# DispenserV2_0.net
KiCad netlist of a schematic drawn in EAGLE
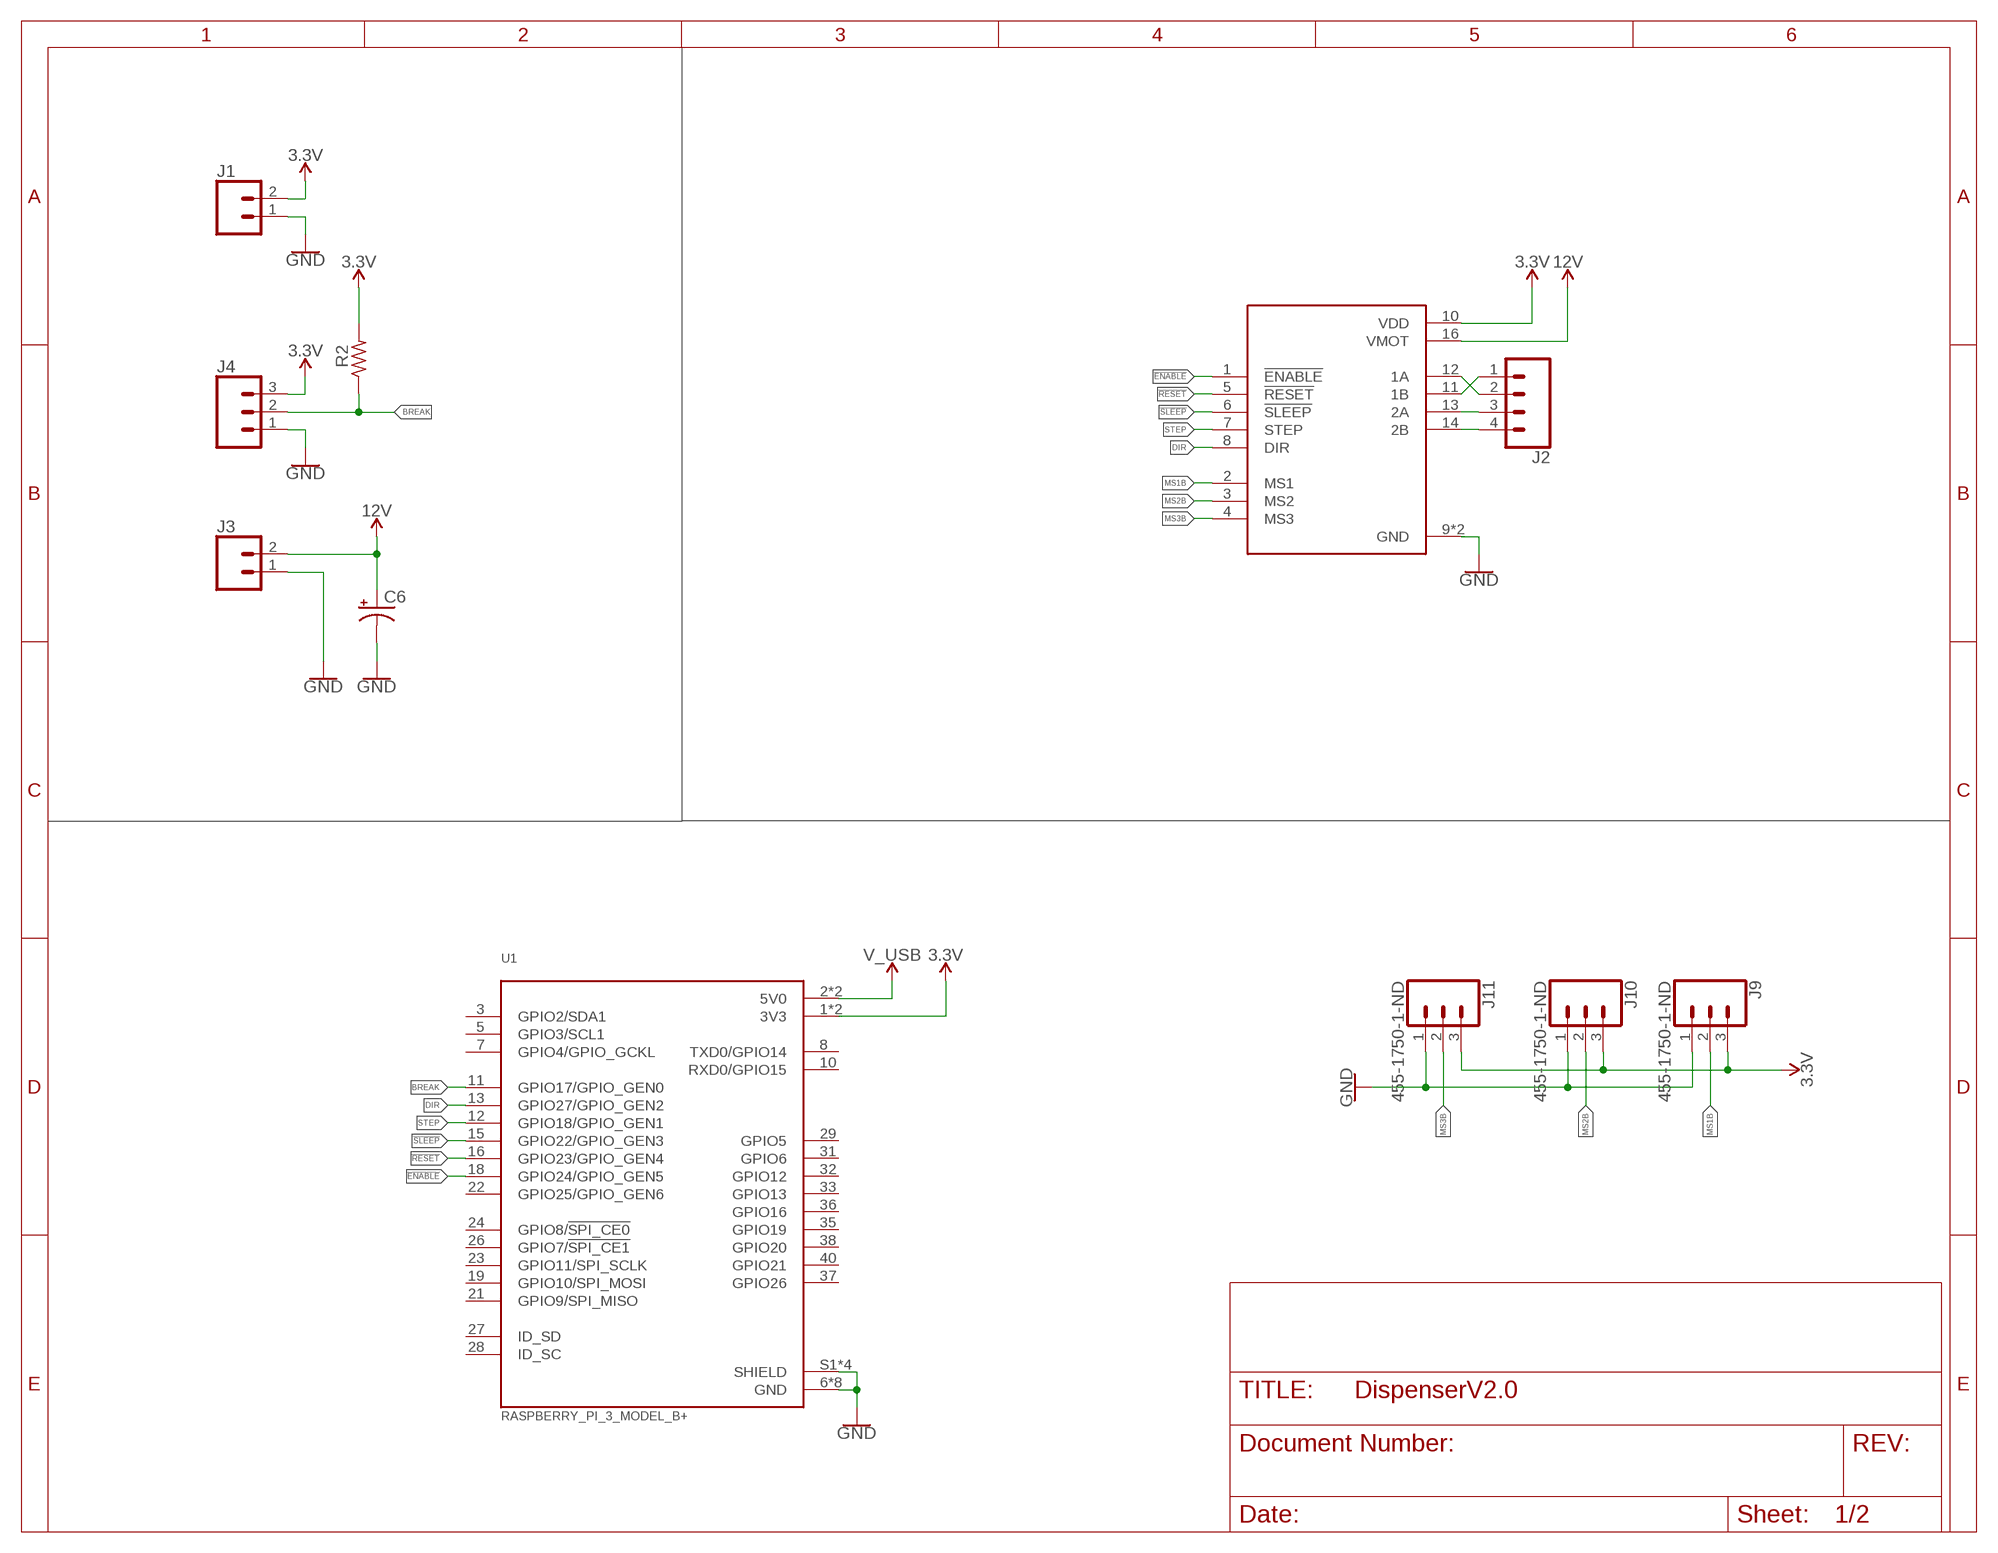
[diagram p0: schematic, sheet 1]
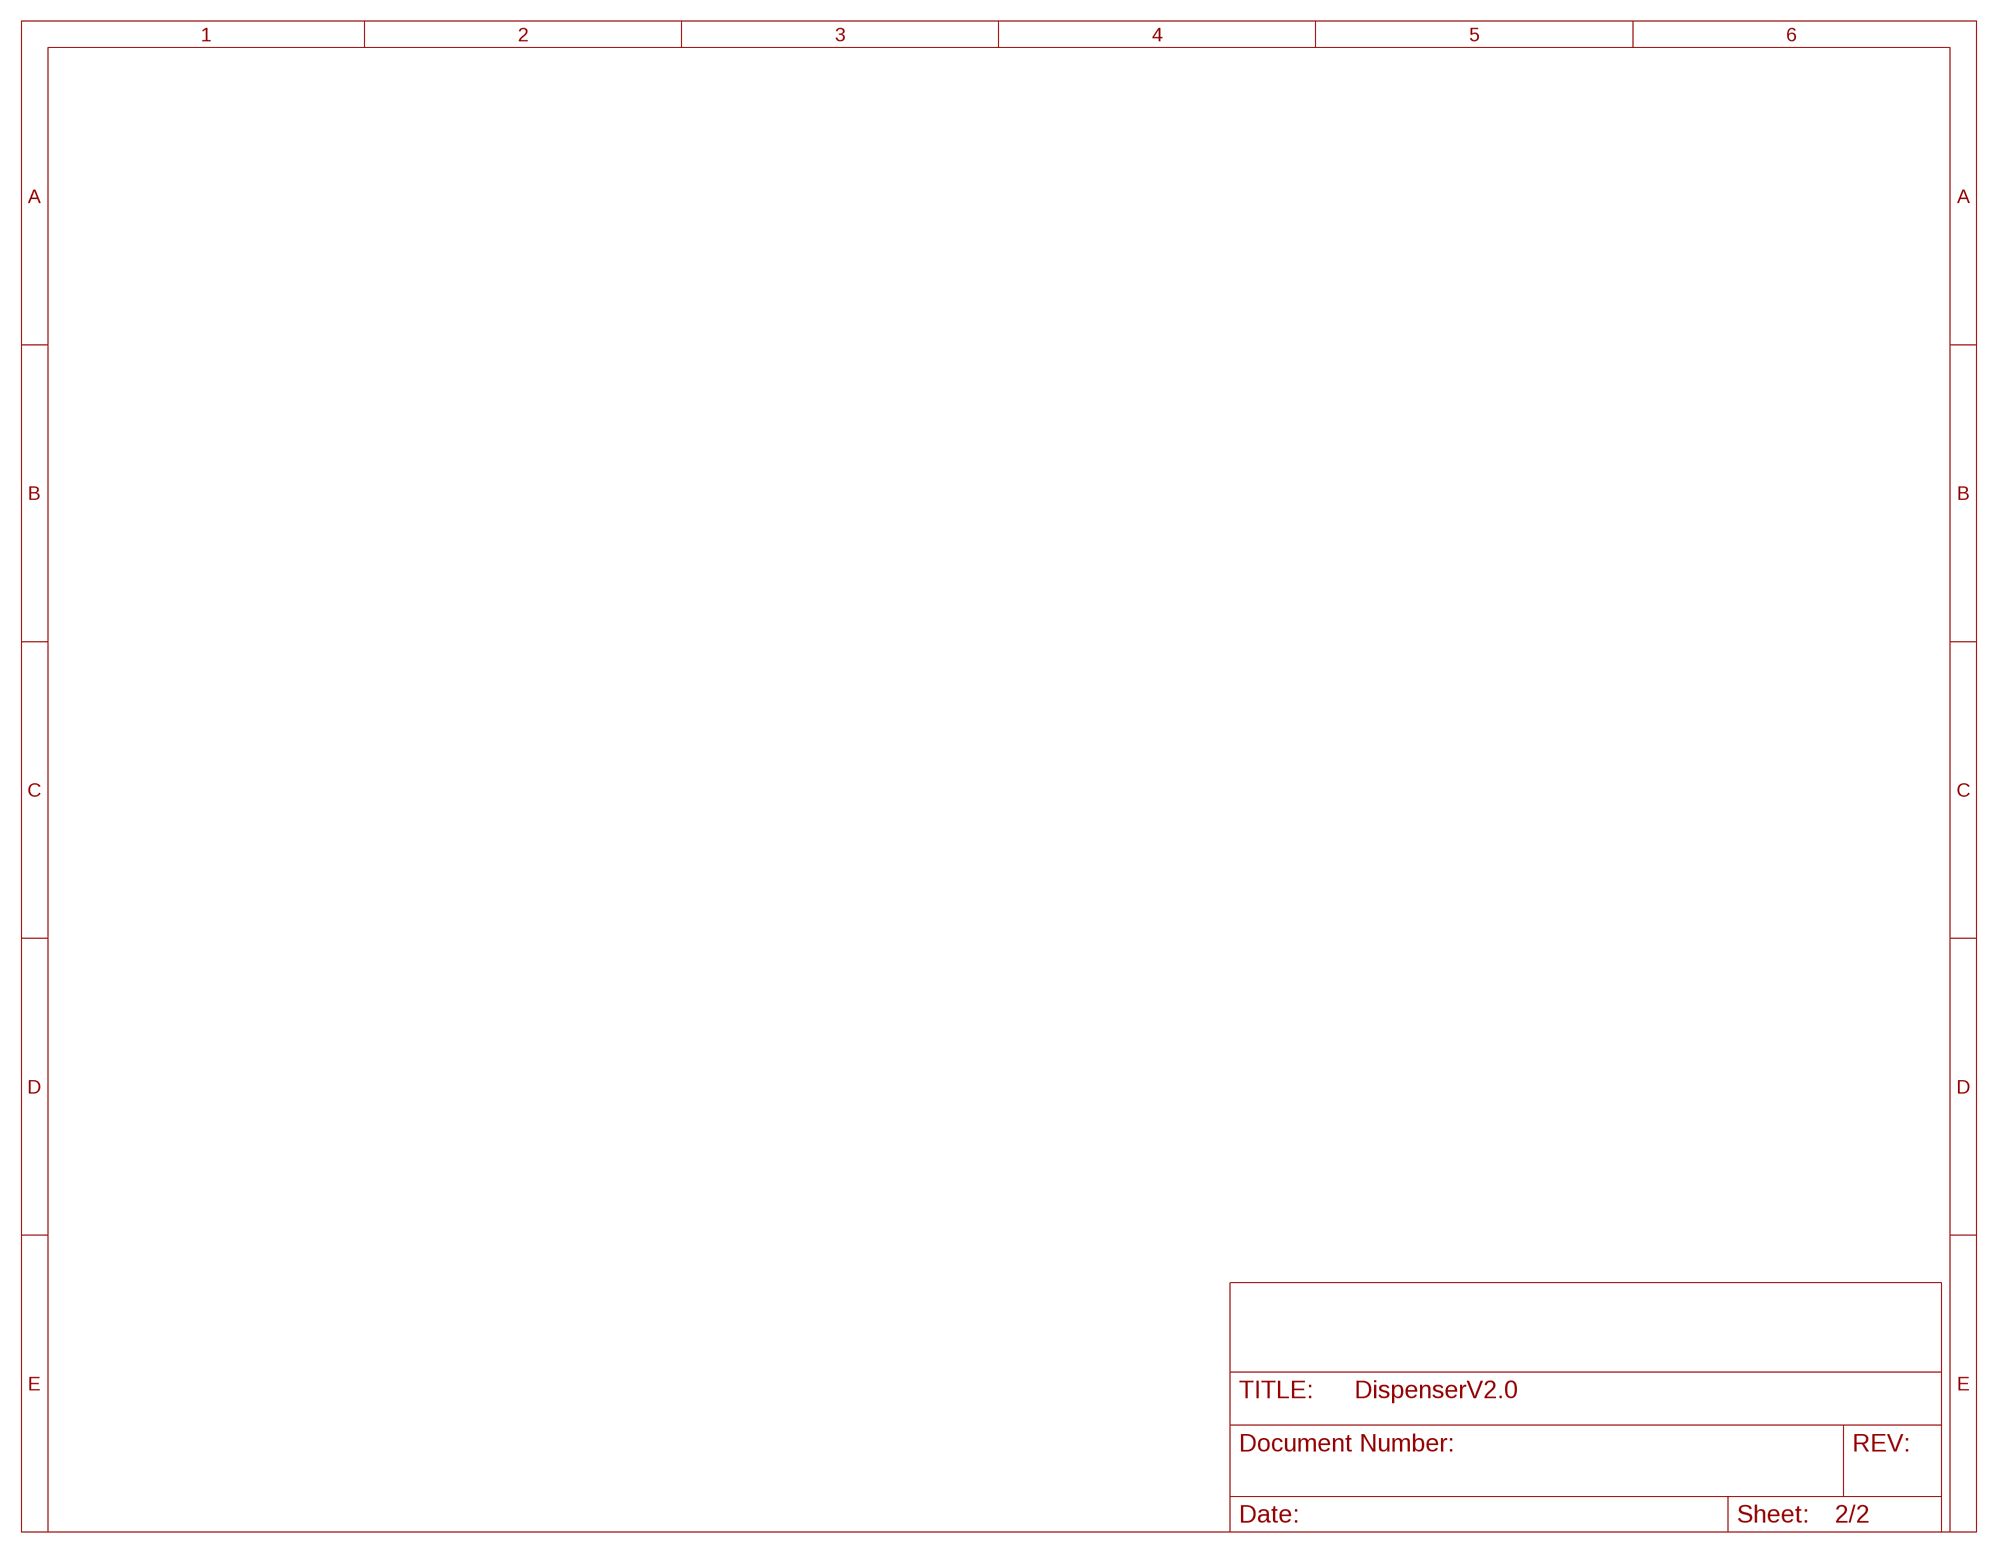
[diagram p1: schematic, sheet 2]

(export (version "E")
  (design (tool "Eeschema 10.0.6"))
  (components
    (comp (ref "C6")
      (value "CPOL-USE2-5")
      (footprint "eagle-import:E2-5")
      (libsource (lib "eagle-import") (part "CPOL-USE2-5"))
    )
    (comp (ref "J1")
      (value "CONN_023.5MM")
      (footprint "eagle-import:SCREWTERMINAL-3.5MM-2")
      (libsource (lib "eagle-import") (part "CONN_023.5MM"))
    )
    (comp (ref "J2")
      (value "CONN_04")
      (footprint "eagle-import:1X04")
      (libsource (lib "eagle-import") (part "CONN_04"))
    )
    (comp (ref "J3")
      (value "CONN_023.5MM")
      (footprint "eagle-import:SCREWTERMINAL-3.5MM-2")
      (libsource (lib "eagle-import") (part "CONN_023.5MM"))
    )
    (comp (ref "J4")
      (value "CONN_03SCREW")
      (footprint "eagle-import:SCREWTERMINAL-3.5MM-3")
      (libsource (lib "eagle-import") (part "CONN_03SCREW"))
    )
    (comp (ref "J9")
      (value "455-1750-1-ND")
      (footprint "eagle-import:1X03")
      (libsource (lib "eagle-import") (part "CONN_03"))
    )
    (comp (ref "J10")
      (value "455-1750-1-ND")
      (footprint "eagle-import:1X03")
      (libsource (lib "eagle-import") (part "CONN_03"))
    )
    (comp (ref "J11")
      (value "455-1750-1-ND")
      (footprint "eagle-import:1X03")
      (libsource (lib "eagle-import") (part "CONN_03"))
    )
    (comp (ref "R2")
      (value "R-US_0207/10")
      (footprint "eagle-import:0207_10")
      (libsource (lib "eagle-import") (part "R-US_0207/10"))
    )
    (comp (ref "U1")
      (value "RASPBERRY_PI_3_MODEL_B+")
      (footprint "eagle-import:MODULE_RASPBERRY_PI_3_MODEL_B+")
      (fields (field (name "MF") "Raspberry Pi") (field (name "MP") "RASPBERRY PI 3 MODEL B+"))
      (libsource (lib "eagle-import") (part "RASPBERRY_PI_3_MODEL_B+"))
    )
    (comp (ref "U2")
      (value "A4988")
      (footprint "eagle-import:MODULE_A4988_STEPPER_MOTOR_DRIVER_CARRIER")
      (fields (field (name "MF") "Pololu") (field (name "MP") "A4988 STEPPER MOTOR DRIVER CARRIER"))
      (libsource (lib "eagle-import") (part "A4988_STEPPER_MOTOR_DRIVER_CARRIER"))
    )
  )
  (nets
    (net (code "1") (name "3.3V") (class "Default")
      (node (ref "J1") (pin "2") (pinfunction "2_2") (pintype "passive"))
      (node (ref "J10") (pin "3") (pinfunction "3_3") (pintype "passive"))
      (node (ref "J11") (pin "3") (pinfunction "3_3") (pintype "passive"))
      (node (ref "J4") (pin "3") (pinfunction "3_3") (pintype "passive"))
      (node (ref "J9") (pin "3") (pinfunction "3_3") (pintype "passive"))
      (node (ref "R2") (pin "2") (pinfunction "2_2") (pintype "passive"))
      (node (ref "U1") (pin "1") (pinfunction "3V3_1") (pintype "power_in"))
      (node (ref "U1") (pin "17") (pinfunction "3V3_17") (pintype "power_in"))
      (node (ref "U2") (pin "10") (pinfunction "VDD_10") (pintype "power_in"))
    )
    (net (code "2") (name "12V") (class "Default")
      (node (ref "C6") (pin "+") (pinfunction "+_+") (pintype "passive"))
      (node (ref "J3") (pin "2") (pinfunction "2_2") (pintype "passive"))
      (node (ref "U2") (pin "16") (pinfunction "VMOT_16") (pintype "power_in"))
    )
    (net (code "3") (name "BREAK") (class "Default")
      (node (ref "J4") (pin "2") (pinfunction "2_2") (pintype "passive"))
      (node (ref "R2") (pin "1") (pinfunction "1_1") (pintype "passive"))
      (node (ref "U1") (pin "11") (pinfunction "GPIO17/GPIO_GEN0_11") (pintype "bidirectional"))
    )
    (net (code "4") (name "DIR") (class "Default")
      (node (ref "U1") (pin "13") (pinfunction "GPIO27/GPIO_GEN2_13") (pintype "bidirectional"))
      (node (ref "U2") (pin "8") (pinfunction "DIR_8") (pintype "input"))
    )
    (net (code "5") (name "GND") (class "Default")
      (node (ref "C6") (pin "-") (pinfunction "-_-") (pintype "passive"))
      (node (ref "J1") (pin "1") (pinfunction "1_1") (pintype "passive"))
      (node (ref "J10") (pin "1") (pinfunction "1_1") (pintype "passive"))
      (node (ref "J11") (pin "1") (pinfunction "1_1") (pintype "passive"))
      (node (ref "J3") (pin "1") (pinfunction "1_1") (pintype "passive"))
      (node (ref "J4") (pin "1") (pinfunction "1_1") (pintype "passive"))
      (node (ref "J9") (pin "1") (pinfunction "1_1") (pintype "passive"))
      (node (ref "U1") (pin "14") (pinfunction "GND_14") (pintype "power_in"))
      (node (ref "U1") (pin "20") (pinfunction "GND_20") (pintype "power_in"))
      (node (ref "U1") (pin "25") (pinfunction "GND_25") (pintype "power_in"))
      (node (ref "U1") (pin "30") (pinfunction "GND_30") (pintype "power_in"))
      (node (ref "U1") (pin "34") (pinfunction "GND_34") (pintype "power_in"))
      (node (ref "U1") (pin "39") (pinfunction "GND_39") (pintype "power_in"))
      (node (ref "U1") (pin "6") (pinfunction "GND_6") (pintype "power_in"))
      (node (ref "U1") (pin "9") (pinfunction "GND_9") (pintype "power_in"))
      (node (ref "U1") (pin "S1") (pinfunction "SHIELD_S1") (pintype "power_in"))
      (node (ref "U1") (pin "S2") (pinfunction "SHIELD_S2") (pintype "power_in"))
      (node (ref "U1") (pin "S3") (pinfunction "SHIELD_S3") (pintype "power_in"))
      (node (ref "U1") (pin "S4") (pinfunction "SHIELD_S4") (pintype "power_in"))
      (node (ref "U2") (pin "15") (pinfunction "GND_15") (pintype "power_in"))
      (node (ref "U2") (pin "9") (pinfunction "GND_9") (pintype "power_in"))
    )
    (net (code "6") (name "MS1B") (class "Default")
      (node (ref "J9") (pin "2") (pinfunction "2_2") (pintype "passive"))
      (node (ref "U2") (pin "2") (pinfunction "MS1_2") (pintype "input"))
    )
    (net (code "7") (name "MS2B") (class "Default")
      (node (ref "J10") (pin "2") (pinfunction "2_2") (pintype "passive"))
      (node (ref "U2") (pin "3") (pinfunction "MS2_3") (pintype "input"))
    )
    (net (code "8") (name "MS3B") (class "Default")
      (node (ref "J11") (pin "2") (pinfunction "2_2") (pintype "passive"))
      (node (ref "U2") (pin "4") (pinfunction "MS3_4") (pintype "input"))
    )
    (net (code "9") (name "Net-(U2-1A)") (class "Default")
      (node (ref "J2") (pin "2") (pinfunction "2_2") (pintype "passive"))
      (node (ref "U2") (pin "12") (pinfunction "1A_12") (pintype "output"))
    )
    (net (code "10") (name "Net-(U2-1B)") (class "Default")
      (node (ref "J2") (pin "1") (pinfunction "1_1") (pintype "passive"))
      (node (ref "U2") (pin "11") (pinfunction "1B_11") (pintype "output"))
    )
    (net (code "11") (name "Net-(U2-2A)") (class "Default")
      (node (ref "J2") (pin "3") (pinfunction "3_3") (pintype "passive"))
      (node (ref "U2") (pin "13") (pinfunction "2A_13") (pintype "output"))
    )
    (net (code "12") (name "Net-(U2-2B)") (class "Default")
      (node (ref "J2") (pin "4") (pinfunction "4_4") (pintype "passive"))
      (node (ref "U2") (pin "14") (pinfunction "2B_14") (pintype "output"))
    )
    (net (code "13") (name "STEP") (class "Default")
      (node (ref "U1") (pin "12") (pinfunction "GPIO18/GPIO_GEN1_12") (pintype "bidirectional"))
      (node (ref "U2") (pin "7") (pinfunction "STEP_7") (pintype "input"))
    )
    (net (code "14") (name "V_USB") (class "Default")
      (node (ref "U1") (pin "2") (pinfunction "5V0_2") (pintype "power_in"))
      (node (ref "U1") (pin "4") (pinfunction "5V0_4") (pintype "power_in"))
    )
    (net (code "15") (name "unconnected-(U1-GPIO2{slash}SDA1-Pad3)") (class "Default")
      (node (ref "U1") (pin "3") (pinfunction "GPIO2/SDA1_3") (pintype "bidirectional"))
    )
    (net (code "16") (name "unconnected-(U1-GPIO3{slash}SCL1-Pad5)") (class "Default")
      (node (ref "U1") (pin "5") (pinfunction "GPIO3/SCL1_5") (pintype "bidirectional"))
    )
    (net (code "17") (name "unconnected-(U1-GPIO4{slash}GPIO_GCKL-Pad7)") (class "Default")
      (node (ref "U1") (pin "7") (pinfunction "GPIO4/GPIO_GCKL_7") (pintype "bidirectional"))
    )
    (net (code "18") (name "unconnected-(U1-GPIO5-Pad29)") (class "Default")
      (node (ref "U1") (pin "29") (pinfunction "GPIO5_29") (pintype "bidirectional"))
    )
    (net (code "19") (name "unconnected-(U1-GPIO6-Pad31)") (class "Default")
      (node (ref "U1") (pin "31") (pinfunction "GPIO6_31") (pintype "bidirectional"))
    )
    (net (code "20") (name "unconnected-(U1-GPIO7{slash}~{SPI_CE1}-Pad26)") (class "Default")
      (node (ref "U1") (pin "26") (pinfunction "GPIO7/~{SPI_CE1}_26") (pintype "bidirectional"))
    )
    (net (code "21") (name "unconnected-(U1-GPIO8{slash}~{SPI_CE0}-Pad24)") (class "Default")
      (node (ref "U1") (pin "24") (pinfunction "GPIO8/~{SPI_CE0}_24") (pintype "bidirectional"))
    )
    (net (code "22") (name "unconnected-(U1-GPIO9{slash}SPI_MISO-Pad21)") (class "Default")
      (node (ref "U1") (pin "21") (pinfunction "GPIO9/SPI_MISO_21") (pintype "bidirectional"))
    )
    (net (code "23") (name "unconnected-(U1-GPIO10{slash}SPI_MOSI-Pad19)") (class "Default")
      (node (ref "U1") (pin "19") (pinfunction "GPIO10/SPI_MOSI_19") (pintype "bidirectional"))
    )
    (net (code "24") (name "unconnected-(U1-GPIO11{slash}SPI_SCLK-Pad23)") (class "Default")
      (node (ref "U1") (pin "23") (pinfunction "GPIO11/SPI_SCLK_23") (pintype "bidirectional"))
    )
    (net (code "25") (name "unconnected-(U1-GPIO12-Pad32)") (class "Default")
      (node (ref "U1") (pin "32") (pinfunction "GPIO12_32") (pintype "bidirectional"))
    )
    (net (code "26") (name "unconnected-(U1-GPIO13-Pad33)") (class "Default")
      (node (ref "U1") (pin "33") (pinfunction "GPIO13_33") (pintype "bidirectional"))
    )
    (net (code "27") (name "unconnected-(U1-GPIO16-Pad36)") (class "Default")
      (node (ref "U1") (pin "36") (pinfunction "GPIO16_36") (pintype "bidirectional"))
    )
    (net (code "28") (name "unconnected-(U1-GPIO19-Pad35)") (class "Default")
      (node (ref "U1") (pin "35") (pinfunction "GPIO19_35") (pintype "bidirectional"))
    )
    (net (code "29") (name "unconnected-(U1-GPIO20-Pad38)") (class "Default")
      (node (ref "U1") (pin "38") (pinfunction "GPIO20_38") (pintype "bidirectional"))
    )
    (net (code "30") (name "unconnected-(U1-GPIO21-Pad40)") (class "Default")
      (node (ref "U1") (pin "40") (pinfunction "GPIO21_40") (pintype "bidirectional"))
    )
    (net (code "31") (name "unconnected-(U1-GPIO25{slash}GPIO_GEN6-Pad22)") (class "Default")
      (node (ref "U1") (pin "22") (pinfunction "GPIO25/GPIO_GEN6_22") (pintype "bidirectional"))
    )
    (net (code "32") (name "unconnected-(U1-GPIO26-Pad37)") (class "Default")
      (node (ref "U1") (pin "37") (pinfunction "GPIO26_37") (pintype "bidirectional"))
    )
    (net (code "33") (name "unconnected-(U1-ID_SC-Pad28)") (class "Default")
      (node (ref "U1") (pin "28") (pinfunction "ID_SC_28") (pintype "bidirectional"))
    )
    (net (code "34") (name "unconnected-(U1-ID_SD-Pad27)") (class "Default")
      (node (ref "U1") (pin "27") (pinfunction "ID_SD_27") (pintype "bidirectional"))
    )
    (net (code "35") (name "unconnected-(U1-RXD0{slash}GPIO15-Pad10)") (class "Default")
      (node (ref "U1") (pin "10") (pinfunction "RXD0/GPIO15_10") (pintype "bidirectional"))
    )
    (net (code "36") (name "unconnected-(U1-TXD0{slash}GPIO14-Pad8)") (class "Default")
      (node (ref "U1") (pin "8") (pinfunction "TXD0/GPIO14_8") (pintype "bidirectional"))
    )
    (net (code "37") (name "~{ENABLE}") (class "Default")
      (node (ref "U1") (pin "18") (pinfunction "GPIO24/GPIO_GEN5_18") (pintype "bidirectional"))
      (node (ref "U2") (pin "1") (pinfunction "~{ENABLE}_1") (pintype "input"))
    )
    (net (code "38") (name "~{RESET}") (class "Default")
      (node (ref "U1") (pin "16") (pinfunction "GPIO23/GPIO_GEN4_16") (pintype "bidirectional"))
      (node (ref "U2") (pin "5") (pinfunction "~{RESET}_5") (pintype "input"))
    )
    (net (code "39") (name "~{SLEEP}") (class "Default")
      (node (ref "U1") (pin "15") (pinfunction "GPIO22/GPIO_GEN3_15") (pintype "bidirectional"))
      (node (ref "U2") (pin "6") (pinfunction "~{SLEEP}_6") (pintype "input"))
    )
  )
)
